# 555Astable.net
KiCad netlist of a schematic drawn in EAGLE
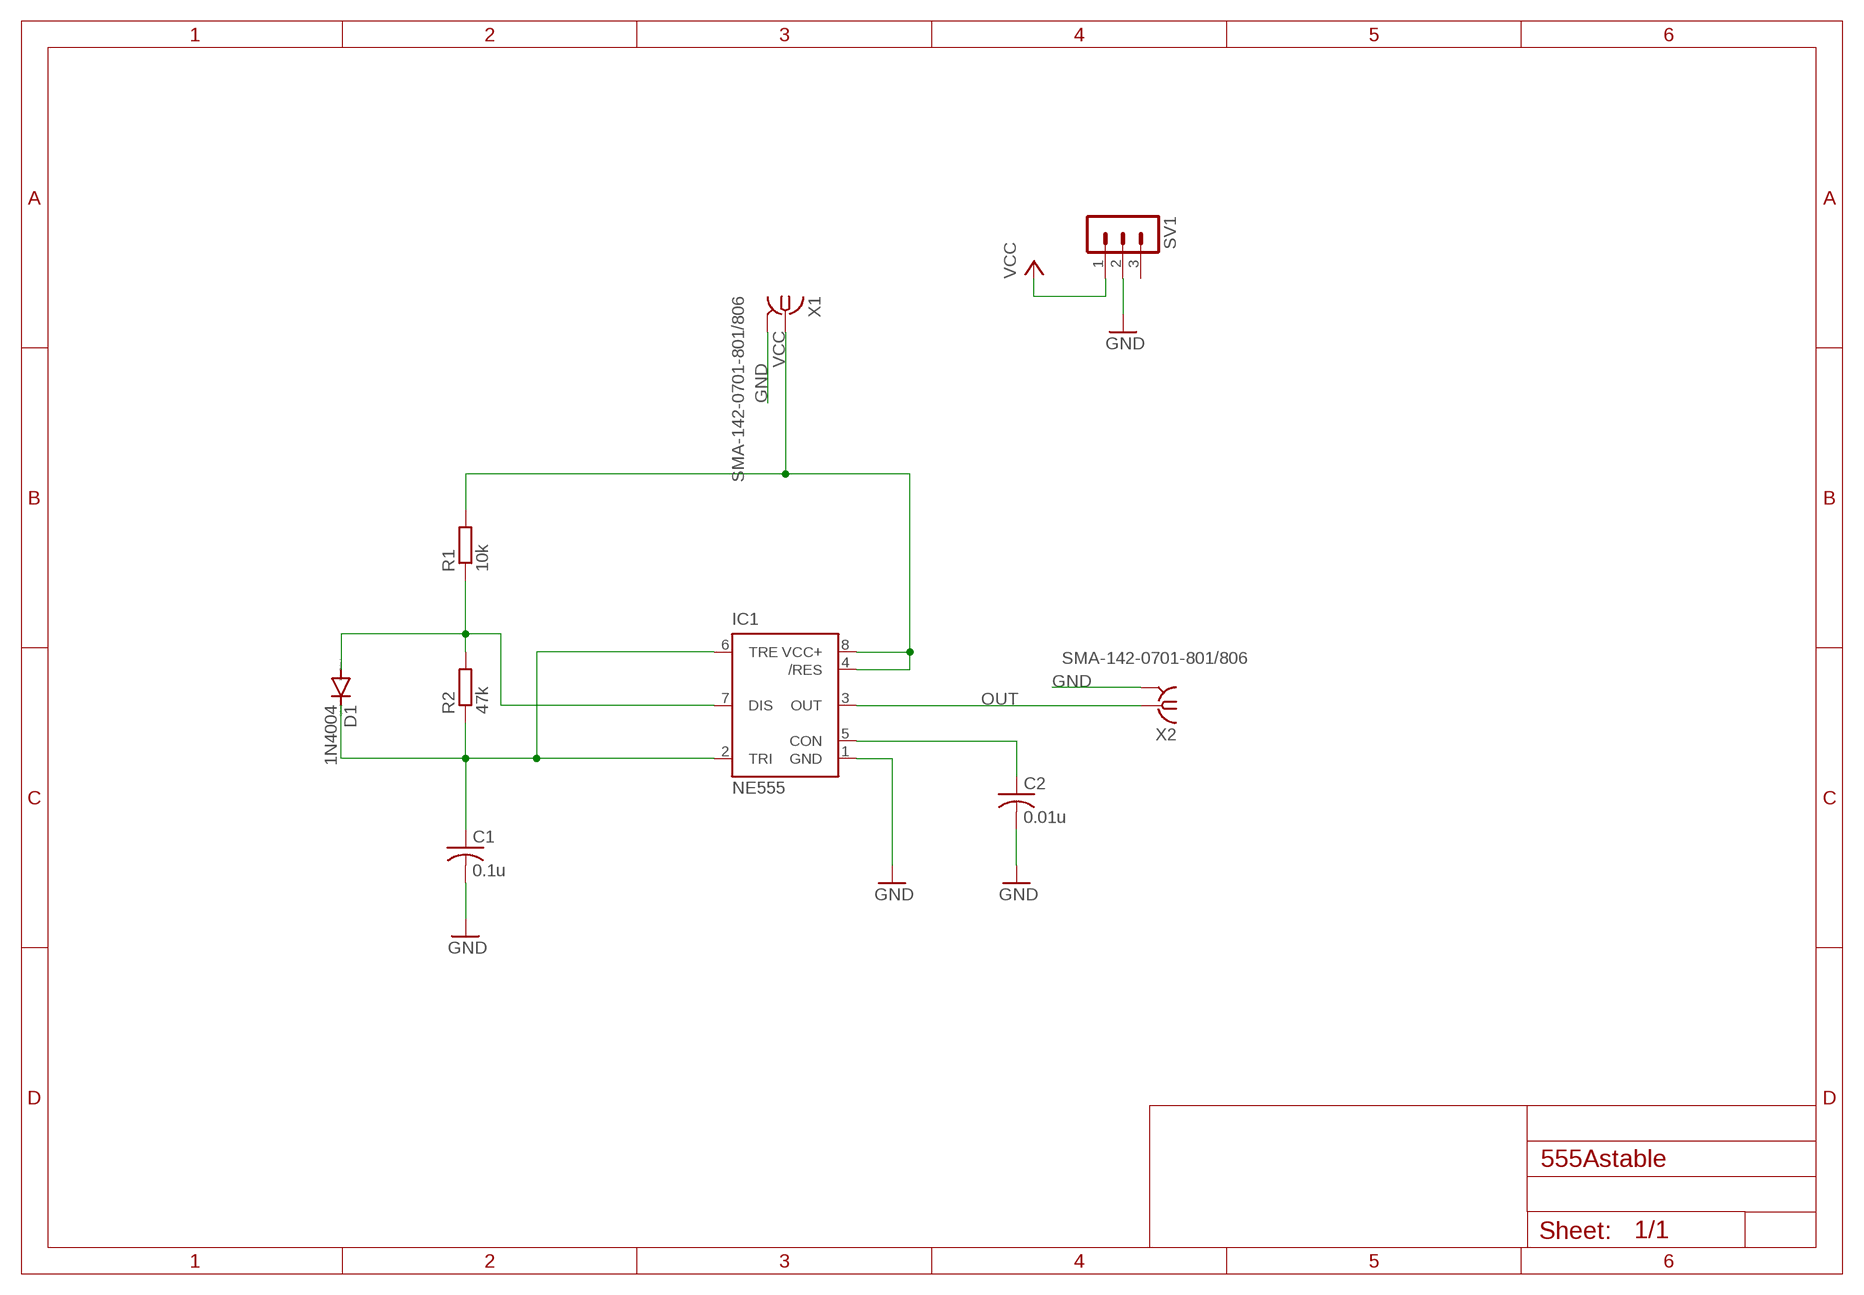
[diagram p0: schematic, sheet 1]

(export (version "E")
  (design (tool "Eeschema 10.0.6"))
  (components
    (comp (ref "C1")
      (value "0.1u")
      (footprint "eagle-import:C0504")
      (libsource (lib "eagle-import") (part "C-USC0504"))
    )
    (comp (ref "C2")
      (value "0.01u")
      (footprint "eagle-import:C0504")
      (libsource (lib "eagle-import") (part "C-USC0504"))
    )
    (comp (ref "D1")
      (value "1N4004")
      (footprint "eagle-import:DO41-10")
      (libsource (lib "eagle-import") (part "1N4004"))
    )
    (comp (ref "IC1")
      (value "NE555")
      (footprint "eagle-import:DIL-08")
      (fields (field (name "MF") "Arrow Electronics") (field (name "MPN") "NE555N"))
      (libsource (lib "eagle-import") (part "NE555"))
    )
    (comp (ref "R1")
      (value "10k")
      (footprint "eagle-import:R0805")
      (libsource (lib "eagle-import") (part "R-EU_R0805"))
    )
    (comp (ref "R2")
      (value "47k")
      (footprint "eagle-import:R0805")
      (libsource (lib "eagle-import") (part "R-EU_R0805"))
    )
    (comp (ref "SV1")
      (value "MA03-1")
      (footprint "eagle-import:MA03-1")
      (libsource (lib "eagle-import") (part "MA03-1"))
    )
    (comp (ref "X1")
      (value "SMA-142-0701-801/806")
      (footprint "eagle-import:J502-ND-142-0701-801_806")
      (fields (field (name "MF") "JOHNSON COMPONENTS") (field (name "MPN") "142-0701-801"))
      (libsource (lib "eagle-import") (part "SMA-142-0701-801/806"))
    )
    (comp (ref "X2")
      (value "SMA-142-0701-801/806")
      (footprint "eagle-import:J502-ND-142-0701-801_806")
      (fields (field (name "MF") "JOHNSON COMPONENTS") (field (name "MPN") "142-0701-801"))
      (libsource (lib "eagle-import") (part "SMA-142-0701-801/806"))
    )
  )
  (nets
    (net (code "1") (name "/OUT") (class "Default")
      (node (ref "IC1") (pin "3") (pinfunction "OUT_3") (pintype "output"))
      (node (ref "X2") (pin "1") (pinfunction "1_1") (pintype "passive"))
    )
    (net (code "2") (name "GND") (class "Default")
      (node (ref "C1") (pin "2") (pinfunction "2_2") (pintype "passive"))
      (node (ref "C2") (pin "2") (pinfunction "2_2") (pintype "passive"))
      (node (ref "IC1") (pin "1") (pinfunction "GND_1") (pintype "power_in"))
      (node (ref "SV1") (pin "2") (pinfunction "2_2") (pintype "passive"))
      (node (ref "X1") (pin "G@1") (pinfunction "2_G@1") (pintype "passive"))
      (node (ref "X1") (pin "G@2") (pinfunction "2_G@2") (pintype "passive"))
      (node (ref "X1") (pin "G@3") (pinfunction "2_G@3") (pintype "passive"))
      (node (ref "X1") (pin "G@4") (pinfunction "2_G@4") (pintype "passive"))
      (node (ref "X2") (pin "G@1") (pinfunction "2_G@1") (pintype "passive"))
      (node (ref "X2") (pin "G@2") (pinfunction "2_G@2") (pintype "passive"))
      (node (ref "X2") (pin "G@3") (pinfunction "2_G@3") (pintype "passive"))
      (node (ref "X2") (pin "G@4") (pinfunction "2_G@4") (pintype "passive"))
    )
    (net (code "3") (name "Net-(IC1-CON)") (class "Default")
      (node (ref "C2") (pin "1") (pinfunction "1_1") (pintype "passive"))
      (node (ref "IC1") (pin "5") (pinfunction "CON_5") (pintype "input"))
    )
    (net (code "4") (name "Net-(IC1-DIS)") (class "Default")
      (node (ref "D1") (pin "A") (pinfunction "A_A") (pintype "passive"))
      (node (ref "IC1") (pin "7") (pinfunction "DIS_7") (pintype "input"))
      (node (ref "R1") (pin "1") (pinfunction "1_1") (pintype "passive"))
      (node (ref "R2") (pin "2") (pinfunction "2_2") (pintype "passive"))
    )
    (net (code "5") (name "Net-(IC1-TRE)") (class "Default")
      (node (ref "C1") (pin "1") (pinfunction "1_1") (pintype "passive"))
      (node (ref "D1") (pin "C") (pinfunction "C_C") (pintype "passive"))
      (node (ref "IC1") (pin "2") (pinfunction "TRI_2") (pintype "input"))
      (node (ref "IC1") (pin "6") (pinfunction "TRE_6") (pintype "input"))
      (node (ref "R2") (pin "1") (pinfunction "1_1") (pintype "passive"))
    )
    (net (code "6") (name "VCC") (class "Default")
      (node (ref "IC1") (pin "4") (pinfunction "/RES_4") (pintype "input"))
      (node (ref "IC1") (pin "8") (pinfunction "VCC+_8") (pintype "power_in"))
      (node (ref "R1") (pin "2") (pinfunction "2_2") (pintype "passive"))
      (node (ref "SV1") (pin "1") (pinfunction "1_1") (pintype "passive"))
      (node (ref "X1") (pin "1") (pinfunction "1_1") (pintype "passive"))
    )
    (net (code "7") (name "unconnected-(SV1-Pad3)") (class "Default")
      (node (ref "SV1") (pin "3") (pinfunction "3_3") (pintype "passive"))
    )
  )
)
